# driver.net
KiCad netlist of a schematic drawn in Altium Designer
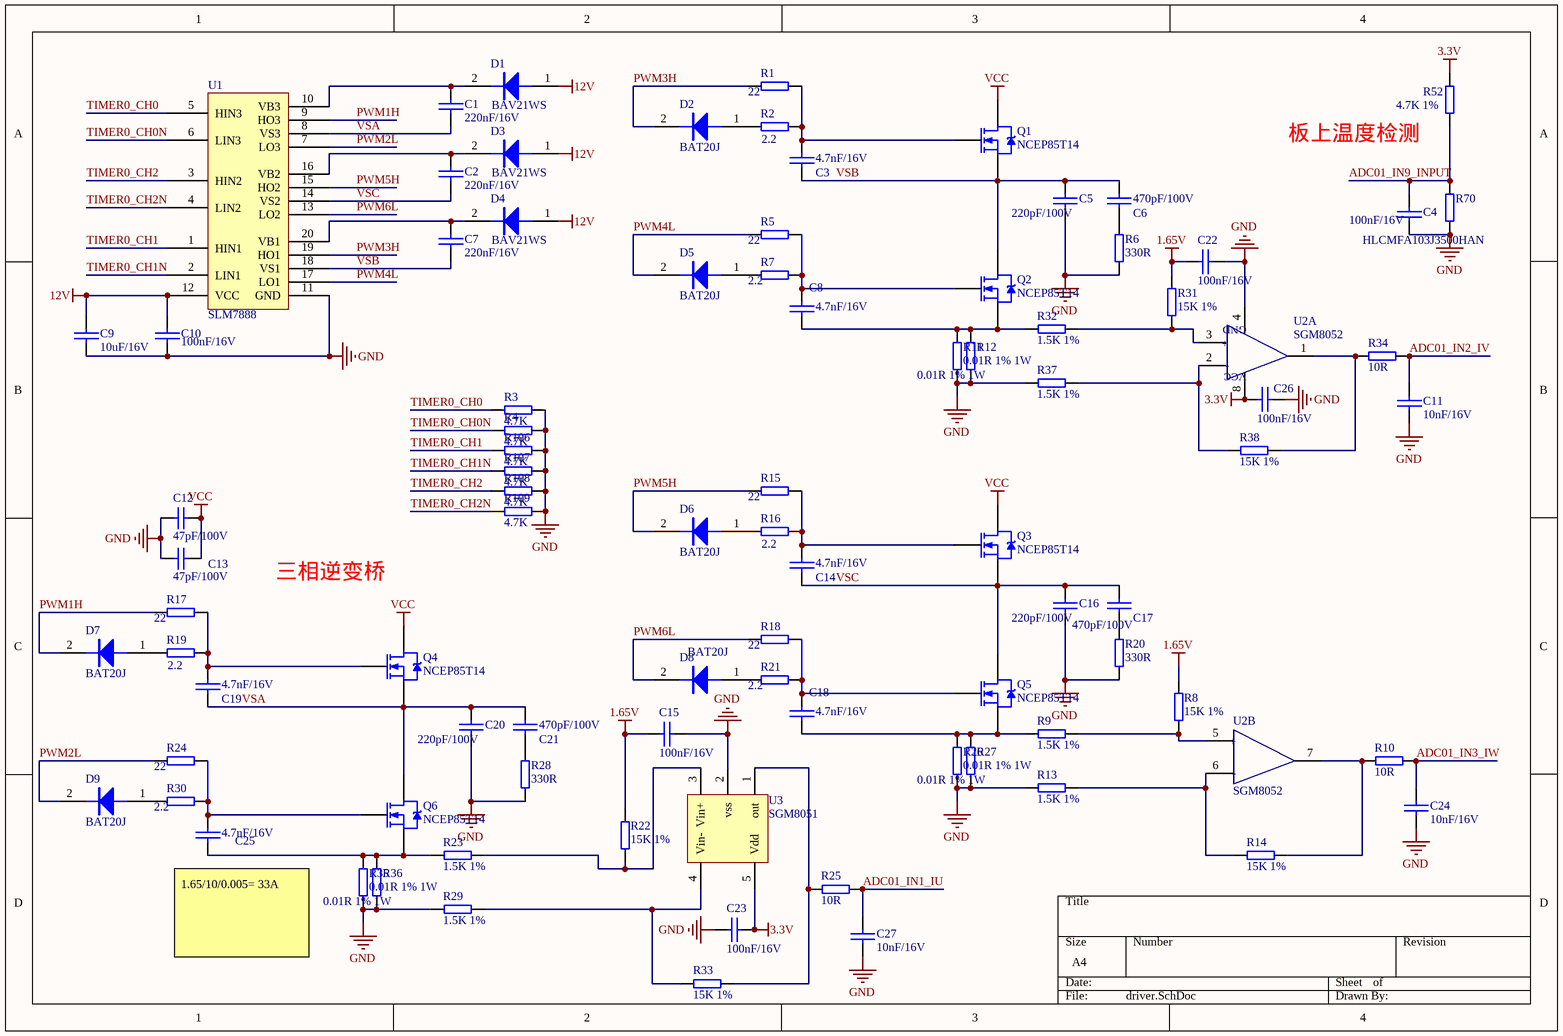
[diagram p0: driver.SchDoc]

(export (version "E")
  (design (tool "Eeschema 10.0.6"))
  (components
    (comp (ref "C1")
      (value "220nF/16V")
      (footprint "C0402")
      (description "Capacitor")
      (libsource (lib "*") (part "CAP"))
    )
    (comp (ref "C2")
      (value "220nF/16V")
      (footprint "C0402")
      (description "Capacitor")
      (libsource (lib "*") (part "CAP"))
    )
    (comp (ref "C3")
      (value "4.7nF/16V")
      (footprint "C0402")
      (description "Capacitor")
      (libsource (lib "*") (part "CAP"))
    )
    (comp (ref "C4")
      (value "100nF/16V")
      (footprint "C0402")
      (description "Capacitor")
      (libsource (lib "*") (part "CAP"))
    )
    (comp (ref "C5")
      (value "220pF/100V")
      (footprint "C0805")
      (description "Capacitor")
      (libsource (lib "*") (part "CAP"))
    )
    (comp (ref "C6")
      (value "470pF/100V")
      (footprint "C0805")
      (description "Capacitor")
      (libsource (lib "*") (part "CAP"))
    )
    (comp (ref "C7")
      (value "220nF/16V")
      (footprint "C0402")
      (description "Capacitor")
      (libsource (lib "*") (part "CAP"))
    )
    (comp (ref "C8")
      (value "4.7nF/16V")
      (footprint "C0402")
      (description "Capacitor")
      (libsource (lib "*") (part "CAP"))
    )
    (comp (ref "C9")
      (value "10uF/16V")
      (footprint "C0805")
      (description "Capacitor")
      (libsource (lib "*") (part "CAP"))
    )
    (comp (ref "C10")
      (value "100nF/16V")
      (footprint "C0603")
      (description "Capacitor")
      (libsource (lib "*") (part "CAP"))
    )
    (comp (ref "C11")
      (value "10nF/16V")
      (footprint "C0402")
      (description "Capacitor")
      (libsource (lib "*") (part "CAP"))
    )
    (comp (ref "C12") (value "47pF/100V") (footprint "C1206") (libsource (lib "zijianku") (part "cap")))
    (comp (ref "C13") (value "47pF/100V") (footprint "C1206") (libsource (lib "zijianku") (part "cap")))
    (comp (ref "C14")
      (value "4.7nF/16V")
      (footprint "C0402")
      (description "Capacitor")
      (libsource (lib "*") (part "CAP"))
    )
    (comp (ref "C15")
      (value "100nF/16V")
      (footprint "C0402")
      (description "Capacitor")
      (libsource (lib "*") (part "CAP"))
    )
    (comp (ref "C16")
      (value "220pF/100V")
      (footprint "C0805")
      (description "Capacitor")
      (libsource (lib "*") (part "CAP"))
    )
    (comp (ref "C17")
      (value "470pF/100V")
      (footprint "C0805")
      (description "Capacitor")
      (libsource (lib "*") (part "CAP"))
    )
    (comp (ref "C18")
      (value "4.7nF/16V")
      (footprint "C0402")
      (description "Capacitor")
      (libsource (lib "*") (part "CAP"))
    )
    (comp (ref "C19")
      (value "4.7nF/16V")
      (footprint "C0402")
      (description "Capacitor")
      (libsource (lib "*") (part "CAP"))
    )
    (comp (ref "C20")
      (value "220pF/100V")
      (footprint "C0805")
      (description "Capacitor")
      (libsource (lib "*") (part "CAP"))
    )
    (comp (ref "C21")
      (value "470pF/100V")
      (footprint "C0805")
      (description "Capacitor")
      (libsource (lib "*") (part "CAP"))
    )
    (comp (ref "C22")
      (value "100nF/16V")
      (footprint "C0402")
      (description "Capacitor")
      (libsource (lib "*") (part "CAP"))
    )
    (comp (ref "C23")
      (value "100nF/16V")
      (footprint "C0402")
      (description "Capacitor")
      (libsource (lib "*") (part "CAP"))
    )
    (comp (ref "C24")
      (value "10nF/16V")
      (footprint "C0402")
      (description "Capacitor")
      (libsource (lib "*") (part "CAP"))
    )
    (comp (ref "C25")
      (value "4.7nF/16V")
      (footprint "C0402")
      (description "Capacitor")
      (libsource (lib "*") (part "CAP"))
    )
    (comp (ref "C26")
      (value "100nF/16V")
      (footprint "C0402")
      (description "Capacitor")
      (libsource (lib "*") (part "CAP"))
    )
    (comp (ref "C27")
      (value "10nF/16V")
      (footprint "C0402")
      (description "Capacitor")
      (libsource (lib "*") (part "CAP"))
    )
    (comp (ref "D1") (value "BAV21WS") (footprint "SOD-323") (libsource (lib "*") (part "DIODE")))
    (comp (ref "D2") (value "BAT20J") (footprint "SOD-323") (libsource (lib "*") (part "DIODE")))
    (comp (ref "D3") (value "BAV21WS") (footprint "SOD-323") (libsource (lib "*") (part "DIODE")))
    (comp (ref "D4") (value "BAV21WS") (footprint "SOD-323") (libsource (lib "*") (part "DIODE")))
    (comp (ref "D5") (value "BAT20J") (footprint "SOD-323") (libsource (lib "*") (part "DIODE")))
    (comp (ref "D6") (value "BAT20J") (footprint "SOD-323") (libsource (lib "*") (part "DIODE")))
    (comp (ref "D7") (value "BAT20J") (footprint "SOD-323") (libsource (lib "*") (part "DIODE")))
    (comp (ref "D8") (value "BAT20J") (footprint "SOD-323") (libsource (lib "*") (part "DIODE")))
    (comp (ref "D9") (value "BAT20J") (footprint "SOD-323") (libsource (lib "*") (part "DIODE")))
    (comp (ref "Q1")
      (value "NCEP85T14")
      (footprint "TO-220ABN")
      (libsource (lib "zijianku") (part "N-channel Enhancement MOS"))
    )
    (comp (ref "Q2")
      (value "NCEP85T14")
      (footprint "TO-220ABN")
      (libsource (lib "zijianku") (part "N-channel Enhancement MOS"))
    )
    (comp (ref "Q3")
      (value "NCEP85T14")
      (footprint "TO-220ABN")
      (libsource (lib "zijianku") (part "N-channel Enhancement MOS"))
    )
    (comp (ref "Q4")
      (value "NCEP85T14")
      (footprint "TO-220ABN")
      (libsource (lib "zijianku") (part "N-channel Enhancement MOS"))
    )
    (comp (ref "Q5")
      (value "NCEP85T14")
      (footprint "TO-220ABN")
      (libsource (lib "zijianku") (part "N-channel Enhancement MOS"))
    )
    (comp (ref "Q6")
      (value "NCEP85T14")
      (footprint "TO-220ABN")
      (libsource (lib "zijianku") (part "N-channel Enhancement MOS"))
    )
    (comp (ref "R1") (value "22") (footprint "R0603") (libsource (lib "*") (part "R")))
    (comp (ref "R2") (value "2.2") (footprint "R0603") (libsource (lib "*") (part "R")))
    (comp (ref "R3") (value "4.7K") (footprint "R0402") (libsource (lib "*") (part "R")))
    (comp (ref "R4") (value "4.7K") (footprint "R0402") (libsource (lib "*") (part "R")))
    (comp (ref "R5") (value "22") (footprint "R0603") (libsource (lib "*") (part "R")))
    (comp (ref "R6") (value "330R") (footprint "R1206") (libsource (lib "zijianku") (part "Resistance")))
    (comp (ref "R7") (value "2.2") (footprint "R0603") (libsource (lib "*") (part "R")))
    (comp (ref "R8") (value "15K 1%") (footprint "R0402") (libsource (lib "zijianku") (part "Resistance")))
    (comp (ref "R9") (value "1.5K 1%") (footprint "R0402") (libsource (lib "zijianku") (part "Resistance")))
    (comp (ref "R10") (value "10R") (footprint "R0402") (libsource (lib "zijianku") (part "Resistance")))
    (comp (ref "R11")
      (value "0.01R 1% 1W")
      (footprint "R1210")
      (libsource (lib "zijianku") (part "Resistance"))
    )
    (comp (ref "R12")
      (value "0.01R 1% 1W")
      (footprint "R1210")
      (libsource (lib "zijianku") (part "Resistance"))
    )
    (comp (ref "R13") (value "1.5K 1%") (footprint "R0402") (libsource (lib "zijianku") (part "Resistance")))
    (comp (ref "R14") (value "15K 1%") (footprint "R0402") (libsource (lib "zijianku") (part "Resistance")))
    (comp (ref "R15") (value "22") (footprint "R0603") (libsource (lib "*") (part "R")))
    (comp (ref "R16") (value "2.2") (footprint "R0603") (libsource (lib "*") (part "R")))
    (comp (ref "R17") (value "22") (footprint "R0603") (libsource (lib "*") (part "R")))
    (comp (ref "R18") (value "22") (footprint "R0603") (libsource (lib "*") (part "R")))
    (comp (ref "R19") (value "2.2") (footprint "R0603") (libsource (lib "*") (part "R")))
    (comp (ref "R20") (value "330R") (footprint "R1206") (libsource (lib "zijianku") (part "Resistance")))
    (comp (ref "R21") (value "2.2") (footprint "R0603") (libsource (lib "*") (part "R")))
    (comp (ref "R22") (value "15K 1%") (footprint "R0402") (libsource (lib "zijianku") (part "Resistance")))
    (comp (ref "R23") (value "1.5K 1%") (footprint "R0402") (libsource (lib "zijianku") (part "Resistance")))
    (comp (ref "R24") (value "22") (footprint "R0603") (libsource (lib "*") (part "R")))
    (comp (ref "R25") (value "10R") (footprint "R0402") (libsource (lib "zijianku") (part "Resistance")))
    (comp (ref "R26")
      (value "0.01R 1% 1W")
      (footprint "R1210")
      (libsource (lib "zijianku") (part "Resistance"))
    )
    (comp (ref "R27")
      (value "0.01R 1% 1W")
      (footprint "R1210")
      (libsource (lib "zijianku") (part "Resistance"))
    )
    (comp (ref "R28") (value "330R") (footprint "R1206") (libsource (lib "zijianku") (part "Resistance")))
    (comp (ref "R29") (value "1.5K 1%") (footprint "R0402") (libsource (lib "zijianku") (part "Resistance")))
    (comp (ref "R30") (value "2.2") (footprint "R0603") (libsource (lib "*") (part "R")))
    (comp (ref "R31") (value "15K 1%") (footprint "R0402") (libsource (lib "zijianku") (part "Resistance")))
    (comp (ref "R32") (value "1.5K 1%") (footprint "R0402") (libsource (lib "zijianku") (part "Resistance")))
    (comp (ref "R33") (value "15K 1%") (footprint "R0402") (libsource (lib "zijianku") (part "Resistance")))
    (comp (ref "R34") (value "10R") (footprint "R0402") (libsource (lib "zijianku") (part "Resistance")))
    (comp (ref "R35")
      (value "0.01R 1% 1W")
      (footprint "R1210")
      (libsource (lib "zijianku") (part "Resistance"))
    )
    (comp (ref "R36")
      (value "0.01R 1% 1W")
      (footprint "R1210")
      (libsource (lib "zijianku") (part "Resistance"))
    )
    (comp (ref "R37") (value "1.5K 1%") (footprint "R0402") (libsource (lib "zijianku") (part "Resistance")))
    (comp (ref "R38") (value "15K 1%") (footprint "R0402") (libsource (lib "zijianku") (part "Resistance")))
    (comp (ref "R52") (value "4.7K 1%") (footprint "R0402") (libsource (lib "*") (part "R")))
    (comp (ref "R70") (value "HLCMFA103J3500HAN") (footprint "R0603") (libsource (lib "*") (part "R")))
    (comp (ref "R106") (value "4.7K") (footprint "R0402") (libsource (lib "*") (part "R")))
    (comp (ref "R107") (value "4.7K") (footprint "R0402") (libsource (lib "*") (part "R")))
    (comp (ref "R108") (value "4.7K") (footprint "R0402") (libsource (lib "*") (part "R")))
    (comp (ref "R109") (value "4.7K") (footprint "R0402") (libsource (lib "*") (part "R")))
    (comp (ref "U1")
      (value "SLM7888")
      (footprint "TSSOP-20")
      (description "SILLUMIN")
      (libsource (lib "zijianku") (part "SLM7888"))
    )
    (comp (ref "U2")
      (value "SGM8052")
      (footprint "VSSOP/MSOP-8")
      (description "圣邦微电子")
      (libsource (lib "Common Device") (part "LM393"))
    )
    (comp (ref "U3")
      (value "SGM8051")
      (footprint "SOT-23(5)")
      (description "圣邦微电子")
      (libsource (lib "Common Device") (part "LMV7239"))
    )
  )
  (nets
    (net (code "1") (name "/ADC01_IN1_IU") (class "Default")
      (node (ref "C27") (pin "1") (pinfunction "1_1") (pintype "passive"))
      (node (ref "R25") (pin "1") (pintype "passive"))
    )
    (net (code "2") (name "/ADC01_IN2_IV") (class "Default")
      (node (ref "C11") (pin "1") (pinfunction "1_1") (pintype "passive"))
      (node (ref "R34") (pin "1") (pintype "passive"))
    )
    (net (code "3") (name "/ADC01_IN3_IW") (class "Default")
      (node (ref "C24") (pin "1") (pinfunction "1_1") (pintype "passive"))
      (node (ref "R10") (pin "1") (pintype "passive"))
    )
    (net (code "4") (name "/ADC01_IN9_INPUT") (class "Default")
      (node (ref "C4") (pin "1") (pinfunction "1_1") (pintype "passive"))
      (node (ref "R52") (pin "1") (pinfunction "1_1") (pintype "passive"))
      (node (ref "R70") (pin "2") (pinfunction "2_2") (pintype "passive"))
    )
    (net (code "5") (name "/PWM1H") (class "Default")
      (node (ref "D7") (pin "2") (pinfunction "K_2") (pintype "passive"))
      (node (ref "R17") (pin "2") (pinfunction "2_2") (pintype "passive"))
      (node (ref "U1") (pin "9") (pinfunction "HO3_9") (pintype "passive"))
    )
    (net (code "6") (name "/PWM2L") (class "Default")
      (node (ref "D9") (pin "2") (pinfunction "K_2") (pintype "passive"))
      (node (ref "R24") (pin "2") (pinfunction "2_2") (pintype "passive"))
      (node (ref "U1") (pin "7") (pinfunction "LO3_7") (pintype "passive"))
    )
    (net (code "7") (name "/PWM3H") (class "Default")
      (node (ref "D2") (pin "2") (pinfunction "K_2") (pintype "passive"))
      (node (ref "R1") (pin "2") (pinfunction "2_2") (pintype "passive"))
      (node (ref "U1") (pin "19") (pinfunction "HO1_19") (pintype "passive"))
    )
    (net (code "8") (name "/PWM4L") (class "Default")
      (node (ref "D5") (pin "2") (pinfunction "K_2") (pintype "passive"))
      (node (ref "R5") (pin "2") (pinfunction "2_2") (pintype "passive"))
      (node (ref "U1") (pin "17") (pinfunction "LO1_17") (pintype "passive"))
    )
    (net (code "9") (name "/PWM5H") (class "Default")
      (node (ref "D6") (pin "2") (pinfunction "K_2") (pintype "passive"))
      (node (ref "R15") (pin "2") (pinfunction "2_2") (pintype "passive"))
      (node (ref "U1") (pin "15") (pinfunction "HO2_15") (pintype "passive"))
    )
    (net (code "10") (name "/PWM6L") (class "Default")
      (node (ref "D8") (pin "2") (pinfunction "K_2") (pintype "passive"))
      (node (ref "R18") (pin "2") (pinfunction "2_2") (pintype "passive"))
      (node (ref "U1") (pin "13") (pinfunction "LO2_13") (pintype "passive"))
    )
    (net (code "11") (name "/TIMER0_CH0") (class "Default")
      (node (ref "R3") (pin "1") (pinfunction "1_1") (pintype "passive"))
      (node (ref "U1") (pin "5") (pinfunction "HIN3_5") (pintype "passive"))
    )
    (net (code "12") (name "/TIMER0_CH0N") (class "Default")
      (node (ref "R4") (pin "1") (pinfunction "1_1") (pintype "passive"))
      (node (ref "U1") (pin "6") (pinfunction "LIN3_6") (pintype "passive"))
    )
    (net (code "13") (name "/TIMER0_CH1") (class "Default")
      (node (ref "R106") (pin "1") (pinfunction "1_1") (pintype "passive"))
      (node (ref "U1") (pin "1") (pinfunction "HIN1_1") (pintype "passive"))
    )
    (net (code "14") (name "/TIMER0_CH1N") (class "Default")
      (node (ref "R107") (pin "1") (pinfunction "1_1") (pintype "passive"))
      (node (ref "U1") (pin "2") (pinfunction "LIN1_2") (pintype "passive"))
    )
    (net (code "15") (name "/TIMER0_CH2") (class "Default")
      (node (ref "R108") (pin "1") (pinfunction "1_1") (pintype "passive"))
      (node (ref "U1") (pin "3") (pinfunction "HIN2_3") (pintype "passive"))
    )
    (net (code "16") (name "/TIMER0_CH2N") (class "Default")
      (node (ref "R109") (pin "1") (pinfunction "1_1") (pintype "passive"))
      (node (ref "U1") (pin "4") (pinfunction "LIN2_4") (pintype "passive"))
    )
    (net (code "17") (name "/VSA") (class "Default")
      (node (ref "C1") (pin "1") (pinfunction "1_1") (pintype "passive"))
      (node (ref "C19") (pin "2") (pinfunction "2_2") (pintype "passive"))
      (node (ref "C20") (pin "2") (pinfunction "2_2") (pintype "passive"))
      (node (ref "C21") (pin "1") (pinfunction "1_1") (pintype "passive"))
      (node (ref "Q4") (pin "2") (pinfunction "S_2") (pintype "passive"))
      (node (ref "Q6") (pin "3") (pinfunction "D_3") (pintype "passive"))
      (node (ref "U1") (pin "8") (pinfunction "VS3_8") (pintype "passive"))
    )
    (net (code "18") (name "/VSB") (class "Default")
      (node (ref "C3") (pin "2") (pinfunction "2_2") (pintype "passive"))
      (node (ref "C5") (pin "2") (pinfunction "2_2") (pintype "passive"))
      (node (ref "C6") (pin "1") (pinfunction "1_1") (pintype "passive"))
      (node (ref "C7") (pin "1") (pinfunction "1_1") (pintype "passive"))
      (node (ref "Q1") (pin "2") (pinfunction "S_2") (pintype "passive"))
      (node (ref "Q2") (pin "3") (pinfunction "D_3") (pintype "passive"))
      (node (ref "U1") (pin "18") (pinfunction "VS1_18") (pintype "passive"))
    )
    (net (code "19") (name "/VSC") (class "Default")
      (node (ref "C14") (pin "2") (pinfunction "2_2") (pintype "passive"))
      (node (ref "C16") (pin "2") (pinfunction "2_2") (pintype "passive"))
      (node (ref "C17") (pin "1") (pinfunction "1_1") (pintype "passive"))
      (node (ref "C2") (pin "1") (pinfunction "1_1") (pintype "passive"))
      (node (ref "Q3") (pin "2") (pinfunction "S_2") (pintype "passive"))
      (node (ref "Q5") (pin "3") (pinfunction "D_3") (pintype "passive"))
      (node (ref "U1") (pin "14") (pinfunction "VS2_14") (pintype "passive"))
    )
    (net (code "20") (name "1.65V") (class "Default")
      (node (ref "C15") (pin "2") (pinfunction "2_2") (pintype "passive"))
      (node (ref "C22") (pin "2") (pinfunction "2_2") (pintype "passive"))
      (node (ref "R22") (pin "1") (pintype "passive"))
      (node (ref "R31") (pin "1") (pintype "passive"))
      (node (ref "R8") (pin "1") (pintype "passive"))
    )
    (net (code "21") (name "3.3V") (class "Default")
      (node (ref "C23") (pin "2") (pinfunction "2_2") (pintype "passive"))
      (node (ref "C26") (pin "2") (pinfunction "2_2") (pintype "passive"))
      (node (ref "R52") (pin "2") (pinfunction "2_2") (pintype "passive"))
      (node (ref "U2") (pin "8") (pinfunction "VCC_8") (pintype "passive"))
      (node (ref "U3") (pin "5") (pinfunction "Vdd_5") (pintype "passive"))
    )
    (net (code "22") (name "12V") (class "Default")
      (node (ref "C10") (pin "2") (pinfunction "2_2") (pintype "passive"))
      (node (ref "C9") (pin "2") (pinfunction "2_2") (pintype "passive"))
      (node (ref "D1") (pin "1") (pinfunction "A_1") (pintype "passive"))
      (node (ref "D3") (pin "1") (pinfunction "A_1") (pintype "passive"))
      (node (ref "D4") (pin "1") (pinfunction "A_1") (pintype "passive"))
      (node (ref "U1") (pin "12") (pinfunction "VCC_12") (pintype "passive"))
    )
    (net (code "23") (name "GND") (class "Default")
      (node (ref "C10") (pin "1") (pinfunction "1_1") (pintype "passive"))
      (node (ref "C11") (pin "2") (pinfunction "2_2") (pintype "passive"))
      (node (ref "C12") (pin "2") (pinfunction "1_2") (pintype "passive"))
      (node (ref "C13") (pin "2") (pinfunction "1_2") (pintype "passive"))
      (node (ref "C15") (pin "1") (pinfunction "1_1") (pintype "passive"))
      (node (ref "C16") (pin "1") (pinfunction "1_1") (pintype "passive"))
      (node (ref "C20") (pin "1") (pinfunction "1_1") (pintype "passive"))
      (node (ref "C22") (pin "1") (pinfunction "1_1") (pintype "passive"))
      (node (ref "C23") (pin "1") (pinfunction "1_1") (pintype "passive"))
      (node (ref "C24") (pin "2") (pinfunction "2_2") (pintype "passive"))
      (node (ref "C26") (pin "1") (pinfunction "1_1") (pintype "passive"))
      (node (ref "C27") (pin "2") (pinfunction "2_2") (pintype "passive"))
      (node (ref "C4") (pin "2") (pinfunction "2_2") (pintype "passive"))
      (node (ref "C5") (pin "1") (pinfunction "1_1") (pintype "passive"))
      (node (ref "C9") (pin "1") (pinfunction "1_1") (pintype "passive"))
      (node (ref "R106") (pin "2") (pinfunction "2_2") (pintype "passive"))
      (node (ref "R107") (pin "2") (pinfunction "2_2") (pintype "passive"))
      (node (ref "R108") (pin "2") (pinfunction "2_2") (pintype "passive"))
      (node (ref "R109") (pin "2") (pinfunction "2_2") (pintype "passive"))
      (node (ref "R11") (pin "2") (pintype "passive"))
      (node (ref "R12") (pin "2") (pintype "passive"))
      (node (ref "R13") (pin "2") (pintype "passive"))
      (node (ref "R20") (pin "1") (pintype "passive"))
      (node (ref "R26") (pin "2") (pintype "passive"))
      (node (ref "R27") (pin "2") (pintype "passive"))
      (node (ref "R28") (pin "1") (pintype "passive"))
      (node (ref "R29") (pin "2") (pintype "passive"))
      (node (ref "R3") (pin "2") (pinfunction "2_2") (pintype "passive"))
      (node (ref "R35") (pin "2") (pintype "passive"))
      (node (ref "R36") (pin "2") (pintype "passive"))
      (node (ref "R37") (pin "2") (pintype "passive"))
      (node (ref "R4") (pin "2") (pinfunction "2_2") (pintype "passive"))
      (node (ref "R6") (pin "1") (pintype "passive"))
      (node (ref "R70") (pin "1") (pinfunction "1_1") (pintype "passive"))
      (node (ref "U1") (pin "11") (pinfunction "GND_11") (pintype "passive"))
      (node (ref "U2") (pin "4") (pinfunction "GND_4") (pintype "passive"))
      (node (ref "U3") (pin "2") (pinfunction "vss_2") (pintype "passive"))
    )
    (net (code "24") (name "Net-(C6-Pad2)") (class "Default")
      (node (ref "C6") (pin "2") (pinfunction "2_2") (pintype "passive"))
      (node (ref "R6") (pin "2") (pintype "passive"))
    )
    (net (code "25") (name "Net-(C17-Pad2)") (class "Default")
      (node (ref "C17") (pin "2") (pinfunction "2_2") (pintype "passive"))
      (node (ref "R20") (pin "2") (pintype "passive"))
    )
    (net (code "26") (name "Net-(C21-Pad2)") (class "Default")
      (node (ref "C21") (pin "2") (pinfunction "2_2") (pintype "passive"))
      (node (ref "R28") (pin "2") (pintype "passive"))
    )
    (net (code "27") (name "Net-(D1-K)") (class "Default")
      (node (ref "C1") (pin "2") (pinfunction "2_2") (pintype "passive"))
      (node (ref "D1") (pin "2") (pinfunction "K_2") (pintype "passive"))
      (node (ref "U1") (pin "10") (pinfunction "VB3_10") (pintype "passive"))
    )
    (net (code "28") (name "Net-(D2-A)") (class "Default")
      (node (ref "D2") (pin "1") (pinfunction "A_1") (pintype "passive"))
      (node (ref "R2") (pin "1") (pinfunction "1_1") (pintype "passive"))
    )
    (net (code "29") (name "Net-(D3-K)") (class "Default")
      (node (ref "C2") (pin "2") (pinfunction "2_2") (pintype "passive"))
      (node (ref "D3") (pin "2") (pinfunction "K_2") (pintype "passive"))
      (node (ref "U1") (pin "16") (pinfunction "VB2_16") (pintype "passive"))
    )
    (net (code "30") (name "Net-(D4-K)") (class "Default")
      (node (ref "C7") (pin "2") (pinfunction "2_2") (pintype "passive"))
      (node (ref "D4") (pin "2") (pinfunction "K_2") (pintype "passive"))
      (node (ref "U1") (pin "20") (pinfunction "VB1_20") (pintype "passive"))
    )
    (net (code "31") (name "Net-(D5-A)") (class "Default")
      (node (ref "D5") (pin "1") (pinfunction "A_1") (pintype "passive"))
      (node (ref "R7") (pin "1") (pinfunction "1_1") (pintype "passive"))
    )
    (net (code "32") (name "Net-(D6-A)") (class "Default")
      (node (ref "D6") (pin "1") (pinfunction "A_1") (pintype "passive"))
      (node (ref "R16") (pin "1") (pinfunction "1_1") (pintype "passive"))
    )
    (net (code "33") (name "Net-(D7-A)") (class "Default")
      (node (ref "D7") (pin "1") (pinfunction "A_1") (pintype "passive"))
      (node (ref "R19") (pin "1") (pinfunction "1_1") (pintype "passive"))
    )
    (net (code "34") (name "Net-(D8-A)") (class "Default")
      (node (ref "D8") (pin "1") (pinfunction "A_1") (pintype "passive"))
      (node (ref "R21") (pin "1") (pinfunction "1_1") (pintype "passive"))
    )
    (net (code "35") (name "Net-(D9-A)") (class "Default")
      (node (ref "D9") (pin "1") (pinfunction "A_1") (pintype "passive"))
      (node (ref "R30") (pin "1") (pinfunction "1_1") (pintype "passive"))
    )
    (net (code "36") (name "Net-(Q1-G)") (class "Default")
      (node (ref "C3") (pin "1") (pinfunction "1_1") (pintype "passive"))
      (node (ref "Q1") (pin "1") (pinfunction "G_1") (pintype "passive"))
      (node (ref "R1") (pin "1") (pinfunction "1_1") (pintype "passive"))
      (node (ref "R2") (pin "2") (pinfunction "2_2") (pintype "passive"))
    )
    (net (code "37") (name "Net-(Q2-G)") (class "Default")
      (node (ref "C8") (pin "1") (pinfunction "1_1") (pintype "passive"))
      (node (ref "Q2") (pin "1") (pinfunction "G_1") (pintype "passive"))
      (node (ref "R5") (pin "1") (pinfunction "1_1") (pintype "passive"))
      (node (ref "R7") (pin "2") (pinfunction "2_2") (pintype "passive"))
    )
    (net (code "38") (name "Net-(Q2-S)") (class "Default")
      (node (ref "C8") (pin "2") (pinfunction "2_2") (pintype "passive"))
      (node (ref "Q2") (pin "2") (pinfunction "S_2") (pintype "passive"))
      (node (ref "R11") (pin "1") (pintype "passive"))
      (node (ref "R12") (pin "1") (pintype "passive"))
      (node (ref "R32") (pin "2") (pintype "passive"))
    )
    (net (code "39") (name "Net-(Q3-G)") (class "Default")
      (node (ref "C14") (pin "1") (pinfunction "1_1") (pintype "passive"))
      (node (ref "Q3") (pin "1") (pinfunction "G_1") (pintype "passive"))
      (node (ref "R15") (pin "1") (pinfunction "1_1") (pintype "passive"))
      (node (ref "R16") (pin "2") (pinfunction "2_2") (pintype "passive"))
    )
    (net (code "40") (name "Net-(Q4-G)") (class "Default")
      (node (ref "C19") (pin "1") (pinfunction "1_1") (pintype "passive"))
      (node (ref "Q4") (pin "1") (pinfunction "G_1") (pintype "passive"))
      (node (ref "R17") (pin "1") (pinfunction "1_1") (pintype "passive"))
      (node (ref "R19") (pin "2") (pinfunction "2_2") (pintype "passive"))
    )
    (net (code "41") (name "Net-(Q5-G)") (class "Default")
      (node (ref "C18") (pin "1") (pinfunction "1_1") (pintype "passive"))
      (node (ref "Q5") (pin "1") (pinfunction "G_1") (pintype "passive"))
      (node (ref "R18") (pin "1") (pinfunction "1_1") (pintype "passive"))
      (node (ref "R21") (pin "2") (pinfunction "2_2") (pintype "passive"))
    )
    (net (code "42") (name "Net-(Q5-S)") (class "Default")
      (node (ref "C18") (pin "2") (pinfunction "2_2") (pintype "passive"))
      (node (ref "Q5") (pin "2") (pinfunction "S_2") (pintype "passive"))
      (node (ref "R26") (pin "1") (pintype "passive"))
      (node (ref "R27") (pin "1") (pintype "passive"))
      (node (ref "R9") (pin "2") (pintype "passive"))
    )
    (net (code "43") (name "Net-(Q6-G)") (class "Default")
      (node (ref "C25") (pin "1") (pinfunction "1_1") (pintype "passive"))
      (node (ref "Q6") (pin "1") (pinfunction "G_1") (pintype "passive"))
      (node (ref "R24") (pin "1") (pinfunction "1_1") (pintype "passive"))
      (node (ref "R30") (pin "2") (pinfunction "2_2") (pintype "passive"))
    )
    (net (code "44") (name "Net-(Q6-S)") (class "Default")
      (node (ref "C25") (pin "2") (pinfunction "2_2") (pintype "passive"))
      (node (ref "Q6") (pin "2") (pinfunction "S_2") (pintype "passive"))
      (node (ref "R23") (pin "2") (pintype "passive"))
      (node (ref "R35") (pin "1") (pintype "passive"))
      (node (ref "R36") (pin "1") (pintype "passive"))
    )
    (net (code "45") (name "Net-(R31-Pad2)") (class "Default")
      (node (ref "R31") (pin "2") (pintype "passive"))
      (node (ref "R32") (pin "1") (pintype "passive"))
      (node (ref "U2") (pin "3") (pinfunction "-_3") (pintype "passive"))
    )
    (net (code "46") (name "Net-(R37-Pad1)") (class "Default")
      (node (ref "R37") (pin "1") (pintype "passive"))
      (node (ref "R38") (pin "2") (pintype "passive"))
      (node (ref "U2") (pin "2") (pinfunction "-_2") (pintype "passive"))
    )
    (net (code "47") (name "Net-(U2A-OUT1)") (class "Default")
      (node (ref "R34") (pin "2") (pintype "passive"))
      (node (ref "R38") (pin "1") (pintype "passive"))
      (node (ref "U2") (pin "1") (pinfunction "OUT1_1") (pintype "passive"))
    )
    (net (code "48") (name "Net-(U2B-+)") (class "Default")
      (node (ref "R8") (pin "2") (pintype "passive"))
      (node (ref "R9") (pin "1") (pintype "passive"))
      (node (ref "U2") (pin "5") (pinfunction "+_5") (pintype "passive"))
    )
    (net (code "49") (name "Net-(U2B--)") (class "Default")
      (node (ref "R13") (pin "1") (pintype "passive"))
      (node (ref "R14") (pin "2") (pintype "passive"))
      (node (ref "U2") (pin "6") (pinfunction "-_6") (pintype "passive"))
    )
    (net (code "50") (name "Net-(U2B-OUT2)") (class "Default")
      (node (ref "R10") (pin "2") (pintype "passive"))
      (node (ref "R14") (pin "1") (pintype "passive"))
      (node (ref "U2") (pin "7") (pinfunction "OUT2_7") (pintype "passive"))
    )
    (net (code "51") (name "Net-(U3-Vin+)") (class "Default")
      (node (ref "R22") (pin "2") (pintype "passive"))
      (node (ref "R23") (pin "1") (pintype "passive"))
      (node (ref "U3") (pin "3") (pinfunction "Vin+_3") (pintype "passive"))
    )
    (net (code "52") (name "Net-(U3-Vin-)") (class "Default")
      (node (ref "R29") (pin "1") (pintype "passive"))
      (node (ref "R33") (pin "2") (pintype "passive"))
      (node (ref "U3") (pin "4") (pinfunction "Vin-_4") (pintype "passive"))
    )
    (net (code "53") (name "Net-(U3-out)") (class "Default")
      (node (ref "R25") (pin "2") (pintype "passive"))
      (node (ref "R33") (pin "1") (pintype "passive"))
      (node (ref "U3") (pin "1") (pinfunction "out_1") (pintype "passive"))
    )
    (net (code "54") (name "VCC") (class "Default")
      (node (ref "C12") (pin "1") (pinfunction "0_1") (pintype "passive"))
      (node (ref "C13") (pin "1") (pinfunction "0_1") (pintype "passive"))
      (node (ref "Q1") (pin "3") (pinfunction "D_3") (pintype "passive"))
      (node (ref "Q3") (pin "3") (pinfunction "D_3") (pintype "passive"))
      (node (ref "Q4") (pin "3") (pinfunction "D_3") (pintype "passive"))
    )
  )
)
